# 12_fit_YX.net
KiCad netlist of a schematic drawn in Altium Designer
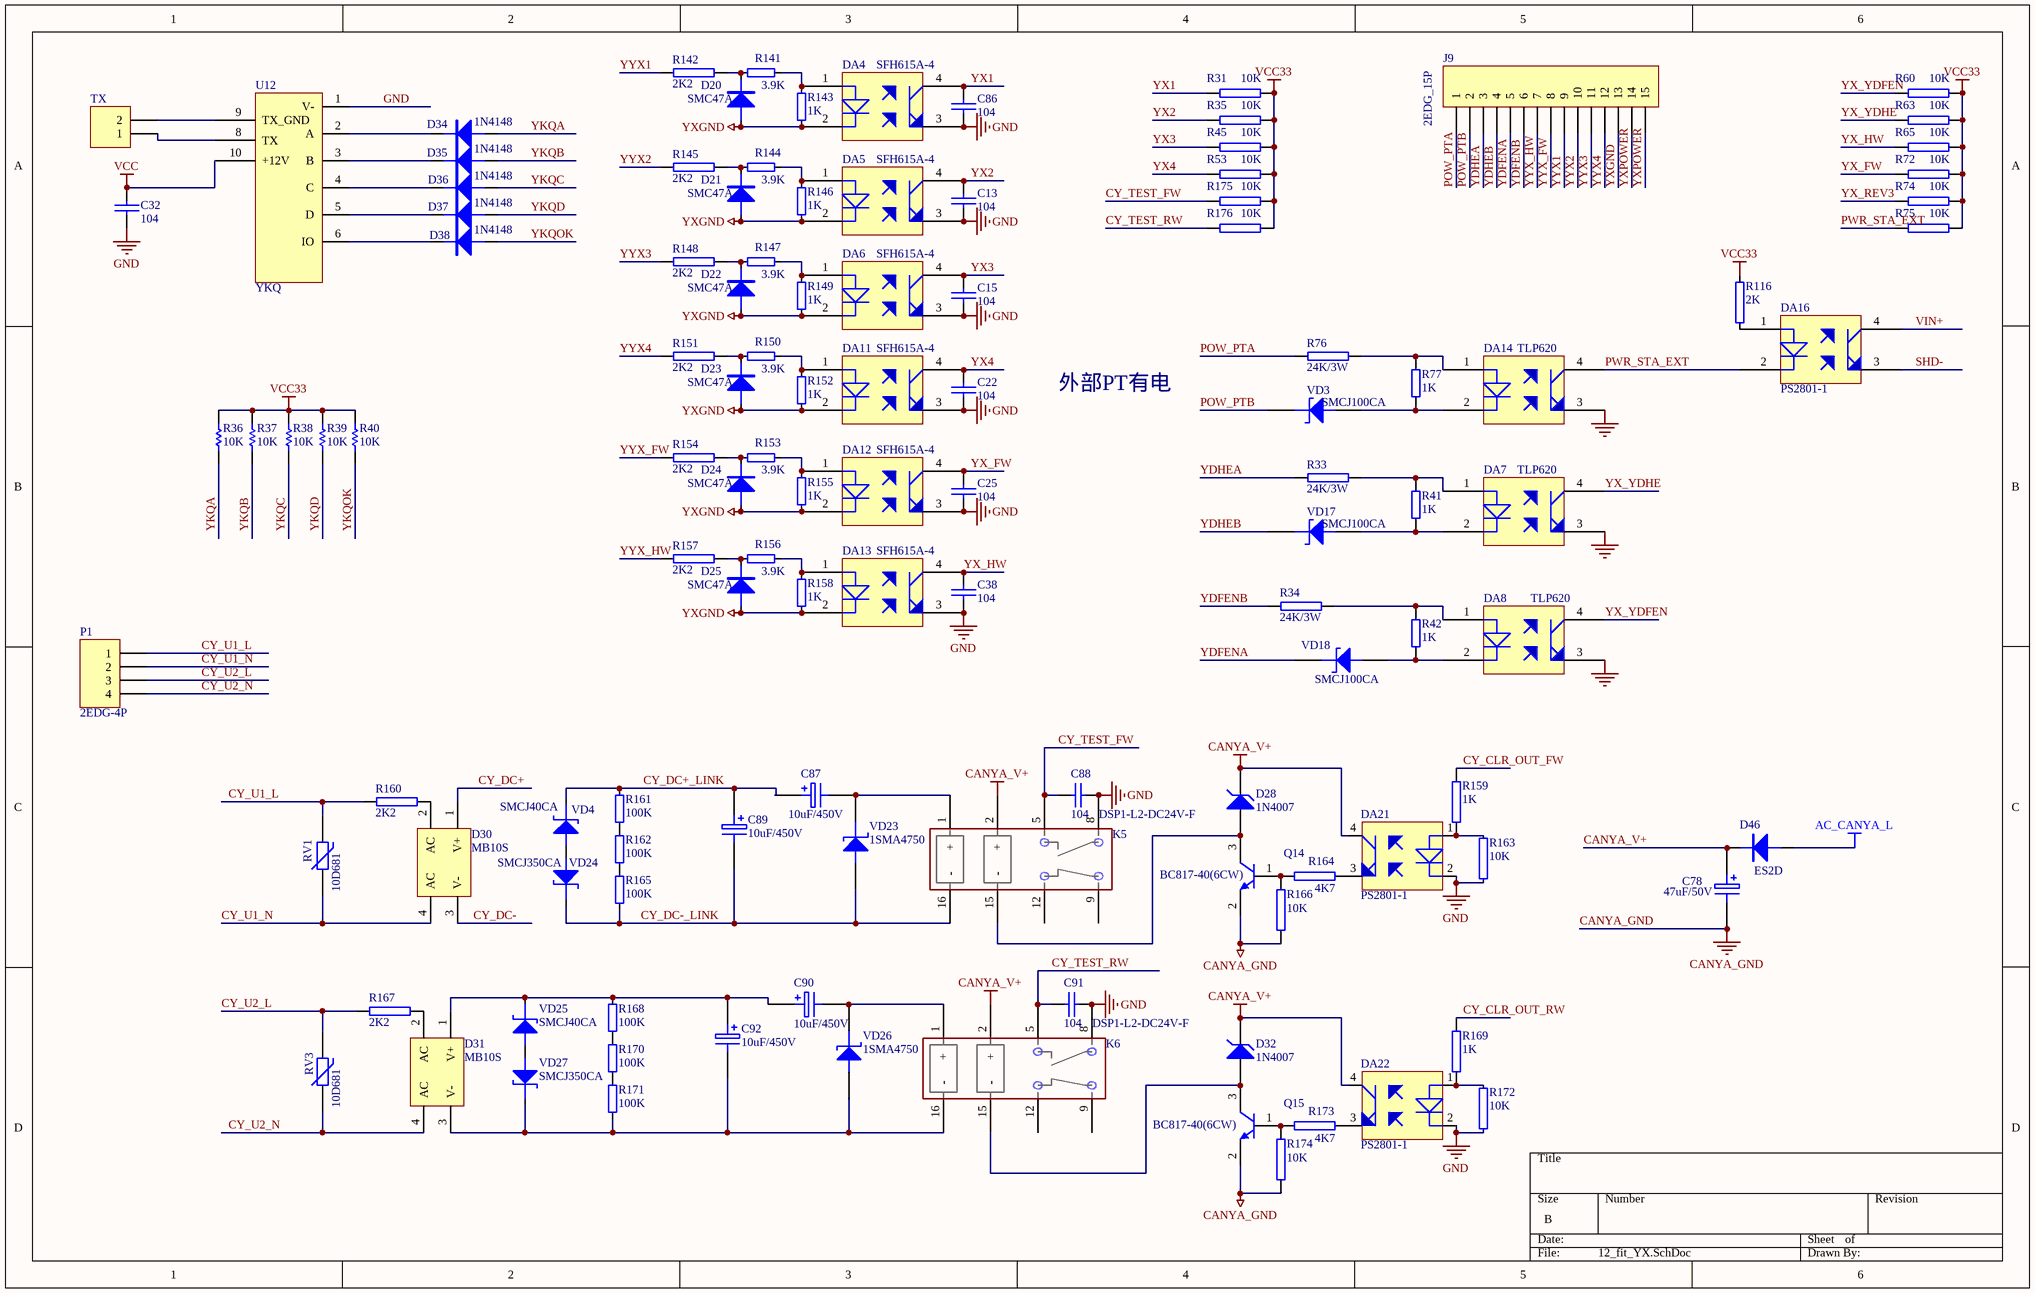
[diagram p0: 12_fit_YX.SchDoc]

(export (version "E")
  (design (tool "Eeschema 10.0.6"))
  (components
    (comp (ref "C13") (value "104") (footprint "smt:C1206") (libsource (lib "*") (part "CAP")))
    (comp (ref "C15") (value "104") (footprint "smt:C1206") (libsource (lib "*") (part "CAP")))
    (comp (ref "C22") (value "104") (footprint "smt:C1206") (libsource (lib "*") (part "CAP")))
    (comp (ref "C25") (value "104") (footprint "smt:C1206") (libsource (lib "*") (part "CAP")))
    (comp (ref "C32") (value "104") (footprint "smt:C1206") (libsource (lib "*") (part "CAP")))
    (comp (ref "C38") (value "104") (footprint "smt:C1206") (libsource (lib "*") (part "CAP")))
    (comp (ref "C78")
      (value "47uF/50V")
      (footprint "smt:47u/50V")
      (description "Electrolytic Capacitor")
      (libsource (lib "*") (part "ELECTRO1"))
    )
    (comp (ref "C86") (value "104") (footprint "smt:C1206") (libsource (lib "*") (part "CAP")))
    (comp (ref "C87")
      (value "10uF/450V")
      (footprint "smt:10u/450V")
      (description "Electrolytic Capacitor")
      (libsource (lib "*") (part "ELECTRO1"))
    )
    (comp (ref "C88") (value "104") (footprint "smt:C1206") (libsource (lib "*") (part "CAP")))
    (comp (ref "C89")
      (value "10uF/450V")
      (footprint "smt:10u/450V")
      (description "Electrolytic Capacitor")
      (libsource (lib "*") (part "ELECTRO1"))
    )
    (comp (ref "C90")
      (value "10uF/450V")
      (footprint "smt:10u/450V")
      (description "Electrolytic Capacitor")
      (libsource (lib "*") (part "ELECTRO1"))
    )
    (comp (ref "C91") (value "104") (footprint "smt:C1206") (libsource (lib "*") (part "CAP")))
    (comp (ref "C92")
      (value "10uF/450V")
      (footprint "smt:10u/450V")
      (description "Electrolytic Capacitor")
      (libsource (lib "*") (part "ELECTRO1"))
    )
    (comp (ref "D20")
      (value "SMC47A")
      (footprint "smt:DO-214AB")
      (description "Diode")
      (libsource (lib "*") (part "DIODE"))
    )
    (comp (ref "D21")
      (value "SMC47A")
      (footprint "smt:DO-214AB")
      (description "Diode")
      (libsource (lib "*") (part "DIODE"))
    )
    (comp (ref "D22")
      (value "SMC47A")
      (footprint "smt:DO-214AB")
      (description "Diode")
      (libsource (lib "*") (part "DIODE"))
    )
    (comp (ref "D23")
      (value "SMC47A")
      (footprint "smt:DO-214AB")
      (description "Diode")
      (libsource (lib "*") (part "DIODE"))
    )
    (comp (ref "D24")
      (value "SMC47A")
      (footprint "smt:DO-214AB")
      (description "Diode")
      (libsource (lib "*") (part "DIODE"))
    )
    (comp (ref "D25")
      (value "SMC47A")
      (footprint "smt:DO-214AB")
      (description "Diode")
      (libsource (lib "*") (part "DIODE"))
    )
    (comp (ref "D28")
      (value "1N4007")
      (footprint "smt:DO-214AC")
      (description "Zener Diode")
      (fields (field (name "PUBLISHER") "Altium Limited"))
      (libsource (lib "Miscellaneous Devices") (part "D Zener"))
    )
    (comp (ref "D30")
      (value "MB10S")
      (footprint "smt:TO-269AA")
      (description "Diode Bridge")
      (fields (field (name "PUBLISHER") "Altium Limited"))
      (libsource (lib "Miscellaneous Devices") (part "Bridge2"))
    )
    (comp (ref "D31")
      (value "MB10S")
      (footprint "smt:TO-269AA")
      (description "Diode Bridge")
      (fields (field (name "PUBLISHER") "Altium Limited"))
      (libsource (lib "Miscellaneous Devices") (part "Bridge2"))
    )
    (comp (ref "D32")
      (value "1N4007")
      (footprint "smt:DO-214AC")
      (description "Zener Diode")
      (fields (field (name "PUBLISHER") "Altium Limited"))
      (libsource (lib "Miscellaneous Devices") (part "D Zener"))
    )
    (comp (ref "D34")
      (value "1N4148")
      (footprint "smt:SMT_4148")
      (description "Diode")
      (libsource (lib "") (part "DIODE_1"))
    )
    (comp (ref "D35")
      (value "1N4148")
      (footprint "smt:SMT_4148")
      (description "Diode")
      (libsource (lib "") (part "DIODE_1"))
    )
    (comp (ref "D36")
      (value "1N4148")
      (footprint "smt:SMT_4148")
      (description "Diode")
      (libsource (lib "") (part "DIODE_1"))
    )
    (comp (ref "D37")
      (value "1N4148")
      (footprint "smt:SMT_4148")
      (description "Diode")
      (libsource (lib "") (part "DIODE_1"))
    )
    (comp (ref "D38")
      (value "1N4148")
      (footprint "smt:SMT_4148")
      (description "Diode")
      (libsource (lib "") (part "DIODE_1"))
    )
    (comp (ref "D46")
      (value "ES2D")
      (footprint "smt:DO-214AA")
      (description "Diode")
      (libsource (lib "") (part "DIODE_1"))
    )
    (comp (ref "DA4") (value "SFH615A-4") (footprint "smt:SFH615A-4") (libsource (lib "*") (part "TLP521-1")))
    (comp (ref "DA5") (value "SFH615A-4") (footprint "smt:SFH615A-4") (libsource (lib "*") (part "TLP521-1")))
    (comp (ref "DA6") (value "SFH615A-4") (footprint "smt:SFH615A-4") (libsource (lib "*") (part "TLP521-1")))
    (comp (ref "DA7") (value "TLP620") (footprint "smt:dip4") (libsource (lib "*") (part "TLP521-1")))
    (comp (ref "DA8") (value "TLP620") (footprint "smt:dip4") (libsource (lib "*") (part "TLP521-1")))
    (comp (ref "DA11")
      (value "SFH615A-4")
      (footprint "smt:SFH615A-4")
      (libsource (lib "*") (part "TLP521-1"))
    )
    (comp (ref "DA12")
      (value "SFH615A-4")
      (footprint "smt:SFH615A-4")
      (libsource (lib "*") (part "TLP521-1"))
    )
    (comp (ref "DA13")
      (value "SFH615A-4")
      (footprint "smt:SFH615A-4")
      (libsource (lib "*") (part "TLP521-1"))
    )
    (comp (ref "DA14") (value "TLP620") (footprint "smt:dip4") (libsource (lib "*") (part "TLP521-1")))
    (comp (ref "DA16") (value "PS2801-1") (footprint "SO-4") (libsource (lib "*") (part "TLP521-1")))
    (comp (ref "DA21") (value "PS2801-1") (footprint "SO-4") (libsource (lib "") (part "TLP521-1_1")))
    (comp (ref "DA22") (value "PS2801-1") (footprint "SO-4") (libsource (lib "") (part "TLP521-1_1")))
    (comp (ref "J9")
      (value "2EDG_15P")
      (footprint "MyCONNECTOR:XR_POWER5.08_15_弯")
      (description "Header, 15-Pin")
      (fields (field (name "PUBLISHER") "Altium Limited"))
      (libsource (lib "Miscellaneous Connectors") (part "Header 15"))
    )
    (comp (ref "K5")
      (value "DSP1-L2-DC24V-F")
      (footprint "DSP1-L2-DC24V-F")
      (libsource (lib "继电器") (part "DSP1-L2-DC24V-F"))
    )
    (comp (ref "K6")
      (value "DSP1-L2-DC24V-F")
      (footprint "DSP1-L2-DC24V-F")
      (libsource (lib "继电器") (part "DSP1-L2-DC24V-F"))
    )
    (comp (ref "P1")
      (value "2EDG-4P")
      (footprint "MyCONNECTOR:XR_POWER5.08_4_弯")
      (description "Header, 4-Pin")
      (fields (field (name "PUBLISHER") "Altium Limited"))
      (libsource (lib "Miscellaneous Connectors") (part "Header 4"))
    )
    (comp (ref "Q14")
      (value "BC817-40(6CW)")
      (footprint "smt:SOT-23")
      (description "NPN")
      (libsource (lib "Miscellaneous Devices LC") (part "SOT-23 2SC3356-T1B-A    S/YS档"))
    )
    (comp (ref "Q15")
      (value "BC817-40(6CW)")
      (footprint "smt:SOT-23")
      (description "NPN")
      (libsource (lib "Miscellaneous Devices LC") (part "SOT-23 2SC3356-T1B-A    S/YS档"))
    )
    (comp (ref "R31") (value "10K") (footprint "smt:R1206") (libsource (lib "*") (part "RES2")))
    (comp (ref "R33") (value "24K/3W") (footprint "smt:res-l5") (libsource (lib "*") (part "RES2")))
    (comp (ref "R34") (value "24K/3W") (footprint "smt:res-l5") (libsource (lib "*") (part "RES2")))
    (comp (ref "R35") (value "10K") (footprint "smt:R1206") (libsource (lib "*") (part "RES2")))
    (comp (ref "R36")
      (value "10K")
      (footprint "smt:R1206")
      (description "Resistor")
      (fields (field (name "PUBLISHER") "Altium Limited"))
      (libsource (lib "Miscellaneous Devices") (part "Res1"))
    )
    (comp (ref "R37")
      (value "10K")
      (footprint "smt:R1206")
      (description "Resistor")
      (fields (field (name "PUBLISHER") "Altium Limited"))
      (libsource (lib "Miscellaneous Devices") (part "Res1"))
    )
    (comp (ref "R38")
      (value "10K")
      (footprint "smt:R1206")
      (description "Resistor")
      (fields (field (name "PUBLISHER") "Altium Limited"))
      (libsource (lib "Miscellaneous Devices") (part "Res1"))
    )
    (comp (ref "R39")
      (value "10K")
      (footprint "smt:R1206")
      (description "Resistor")
      (fields (field (name "PUBLISHER") "Altium Limited"))
      (libsource (lib "Miscellaneous Devices") (part "Res1"))
    )
    (comp (ref "R40")
      (value "10K")
      (footprint "smt:R1206")
      (description "Resistor")
      (fields (field (name "PUBLISHER") "Altium Limited"))
      (libsource (lib "Miscellaneous Devices") (part "Res1"))
    )
    (comp (ref "R41") (value "1K") (footprint "smt:R1206") (libsource (lib "") (part "RES_1")))
    (comp (ref "R42") (value "1K") (footprint "smt:R1206") (libsource (lib "") (part "RES_1")))
    (comp (ref "R45") (value "10K") (footprint "smt:R1206") (libsource (lib "*") (part "RES2")))
    (comp (ref "R53") (value "10K") (footprint "smt:R1206") (libsource (lib "*") (part "RES2")))
    (comp (ref "R60") (value "10K") (footprint "smt:R1206") (libsource (lib "*") (part "RES2")))
    (comp (ref "R63") (value "10K") (footprint "smt:R1206") (libsource (lib "*") (part "RES2")))
    (comp (ref "R65") (value "10K") (footprint "smt:R1206") (libsource (lib "*") (part "RES2")))
    (comp (ref "R72") (value "10K") (footprint "smt:R1206") (libsource (lib "*") (part "RES2")))
    (comp (ref "R74") (value "10K") (footprint "smt:R1206") (libsource (lib "*") (part "RES2")))
    (comp (ref "R75") (value "10K") (footprint "smt:R1206") (libsource (lib "*") (part "RES2")))
    (comp (ref "R76") (value "24K/3W") (footprint "smt:res-l5") (libsource (lib "*") (part "RES2")))
    (comp (ref "R77") (value "1K") (footprint "smt:R1206") (libsource (lib "") (part "RES_1")))
    (comp (ref "R116") (value "2K") (footprint "smt:R1206") (libsource (lib "") (part "RES2_2")))
    (comp (ref "R141") (value "3.9K") (footprint "smt:R1206") (libsource (lib "*") (part "RES")))
    (comp (ref "R142") (value "2K2") (footprint "smt:res_0.5W-L-5.08") (libsource (lib "*") (part "RES2")))
    (comp (ref "R143") (value "1K") (footprint "smt:R1206") (libsource (lib "*") (part "RES")))
    (comp (ref "R144") (value "3.9K") (footprint "smt:R1206") (libsource (lib "*") (part "RES")))
    (comp (ref "R145") (value "2K2") (footprint "smt:res_0.5W-L-5.08") (libsource (lib "*") (part "RES2")))
    (comp (ref "R146") (value "1K") (footprint "smt:R1206") (libsource (lib "*") (part "RES")))
    (comp (ref "R147") (value "3.9K") (footprint "smt:R1206") (libsource (lib "*") (part "RES")))
    (comp (ref "R148") (value "2K2") (footprint "smt:res_0.5W-L-5.08") (libsource (lib "*") (part "RES2")))
    (comp (ref "R149") (value "1K") (footprint "smt:R1206") (libsource (lib "*") (part "RES")))
    (comp (ref "R150") (value "3.9K") (footprint "smt:R1206") (libsource (lib "*") (part "RES")))
    (comp (ref "R151") (value "2K2") (footprint "smt:res_0.5W-L-5.08") (libsource (lib "*") (part "RES2")))
    (comp (ref "R152") (value "1K") (footprint "smt:R1206") (libsource (lib "*") (part "RES")))
    (comp (ref "R153") (value "3.9K") (footprint "smt:R1206") (libsource (lib "*") (part "RES")))
    (comp (ref "R154") (value "2K2") (footprint "smt:res_0.5W-L-5.08") (libsource (lib "*") (part "RES2")))
    (comp (ref "R155") (value "1K") (footprint "smt:R1206") (libsource (lib "*") (part "RES")))
    (comp (ref "R156") (value "3.9K") (footprint "smt:R1206") (libsource (lib "*") (part "RES")))
    (comp (ref "R157") (value "2K2") (footprint "smt:res_0.5W-L-5.08") (libsource (lib "*") (part "RES2")))
    (comp (ref "R158") (value "1K") (footprint "smt:R1206") (libsource (lib "*") (part "RES")))
    (comp (ref "R159") (value "1K") (footprint "smt:R1206") (libsource (lib "*") (part "RES2")))
    (comp (ref "R160") (value "2K2") (footprint "smt:res_0.5W-L-5.08") (libsource (lib "*") (part "RES2")))
    (comp (ref "R161") (value "100K") (footprint "smt:R1206") (libsource (lib "*") (part "RES")))
    (comp (ref "R162") (value "100K") (footprint "smt:R1206") (libsource (lib "*") (part "RES")))
    (comp (ref "R163") (value "10K") (footprint "smt:R1206") (libsource (lib "") (part "RES2_1")))
    (comp (ref "R164") (value "4K7") (footprint "smt:R1206") (libsource (lib "*") (part "RES2")))
    (comp (ref "R165") (value "100K") (footprint "smt:R1206") (libsource (lib "*") (part "RES")))
    (comp (ref "R166") (value "10K") (footprint "smt:R1206") (libsource (lib "*") (part "RES2")))
    (comp (ref "R167") (value "2K2") (footprint "smt:res_0.5W-L-5.08") (libsource (lib "*") (part "RES2")))
    (comp (ref "R168") (value "100K") (footprint "smt:R1206") (libsource (lib "*") (part "RES")))
    (comp (ref "R169") (value "1K") (footprint "smt:R1206") (libsource (lib "*") (part "RES2")))
    (comp (ref "R170") (value "100K") (footprint "smt:R1206") (libsource (lib "*") (part "RES")))
    (comp (ref "R171") (value "100K") (footprint "smt:R1206") (libsource (lib "*") (part "RES")))
    (comp (ref "R172") (value "10K") (footprint "smt:R1206") (libsource (lib "") (part "RES2_1")))
    (comp (ref "R173") (value "4K7") (footprint "smt:R1206") (libsource (lib "*") (part "RES2")))
    (comp (ref "R174") (value "10K") (footprint "smt:R1206") (libsource (lib "*") (part "RES2")))
    (comp (ref "R175") (value "10K") (footprint "smt:R1206") (libsource (lib "*") (part "RES2")))
    (comp (ref "R176") (value "10K") (footprint "smt:R1206") (libsource (lib "*") (part "RES2")))
    (comp (ref "RV1") (value "10D681") (footprint "smt:NTC") (libsource (lib "*") (part "VARISTOR")))
    (comp (ref "RV3") (value "10D681") (footprint "smt:NTC") (libsource (lib "*") (part "VARISTOR")))
    (comp (ref "TX")
      (value "~")
      (footprint "MyCONNECTOR:XH_2.54*2")
      (description "Header, 2-Pin")
      (fields (field (name "PUBLISHER") "Altium Limited"))
      (libsource (lib "Miscellaneous Connectors") (part "Header 2"))
    )
    (comp (ref "U12")
      (value "YKQ")
      (footprint "希瑞模块线路板竖装:YKQ")
      (description "Zener Diode")
      (libsource (lib "*") (part "ZENER3_1"))
    )
    (comp (ref "VD3")
      (value "SMCJ100CA")
      (footprint "smt:DO-214AB")
      (description "双向TVS")
      (libsource (lib "*") (part "ZENER2"))
    )
    (comp (ref "VD4")
      (value "SMCJ40CA")
      (footprint "smt:DO-214AB")
      (description "Zener Diode")
      (libsource (lib "") (part "ZENER2_1"))
    )
    (comp (ref "VD17")
      (value "SMCJ100CA")
      (footprint "smt:DO-214AB")
      (description "双向TVS")
      (libsource (lib "*") (part "ZENER2"))
    )
    (comp (ref "VD18")
      (value "SMCJ100CA")
      (footprint "smt:DO-214AB")
      (description "Zener Diode")
      (libsource (lib "*") (part "ZENER2"))
    )
    (comp (ref "VD23")
      (value "1SMA4750")
      (footprint "smt:DO-214AC")
      (description "Zener Diode")
      (libsource (lib "*") (part "ZENER2"))
    )
    (comp (ref "VD24")
      (value "SMCJ350CA")
      (footprint "smt:DO-214AB")
      (description "Zener Diode")
      (libsource (lib "") (part "ZENER2_1"))
    )
    (comp (ref "VD25")
      (value "SMCJ40CA")
      (footprint "smt:DO-214AB")
      (description "Zener Diode")
      (libsource (lib "") (part "ZENER2_1"))
    )
    (comp (ref "VD26")
      (value "1SMA4750")
      (footprint "smt:DO-214AC")
      (description "Zener Diode")
      (libsource (lib "*") (part "ZENER2"))
    )
    (comp (ref "VD27")
      (value "SMCJ350CA")
      (footprint "smt:DO-214AB")
      (description "Zener Diode")
      (libsource (lib "") (part "ZENER2_1"))
    )
  )
  (nets
    (net (code "1") (name "/CY_CLR_OUT_FW") (class "Default")
      (node (ref "R159") (pin "2") (pintype "passive"))
    )
    (net (code "2") (name "/CY_CLR_OUT_RW") (class "Default")
      (node (ref "R169") (pin "2") (pintype "passive"))
    )
    (net (code "3") (name "/CY_DC+") (class "Default")
      (node (ref "D30") (pin "1") (pinfunction "V+_1") (pintype "passive"))
    )
    (net (code "4") (name "/CY_DC+_LINK") (class "Default")
      (node (ref "C87") (pin "1") (pinfunction "1_1") (pintype "passive"))
      (node (ref "C89") (pin "1") (pinfunction "1_1") (pintype "passive"))
      (node (ref "R161") (pin "2") (pinfunction "2_2") (pintype "passive"))
      (node (ref "VD4") (pin "2") (pinfunction "K_2") (pintype "passive"))
    )
    (net (code "5") (name "/CY_DC-") (class "Default")
      (node (ref "D30") (pin "3") (pinfunction "V-_3") (pintype "passive"))
    )
    (net (code "6") (name "/CY_DC-_LINK") (class "Default")
      (node (ref "C89") (pin "2") (pinfunction "2_2") (pintype "passive"))
      (node (ref "K5") (pin "16") (pinfunction "-_16") (pintype "passive"))
      (node (ref "R165") (pin "1") (pinfunction "1_1") (pintype "passive"))
      (node (ref "VD23") (pin "1") (pinfunction "A_1") (pintype "passive"))
      (node (ref "VD24") (pin "2") (pinfunction "K_2") (pintype "passive"))
    )
    (net (code "7") (name "/CY_TEST_FW") (class "Default")
      (node (ref "C88") (pin "2") (pintype "passive"))
      (node (ref "K5") (pin "5") (pinfunction "NO_5") (pintype "passive"))
      (node (ref "R175") (pin "1") (pintype "passive"))
    )
    (net (code "8") (name "/CY_TEST_RW") (class "Default")
      (node (ref "C91") (pin "2") (pintype "passive"))
      (node (ref "K6") (pin "5") (pinfunction "NO_5") (pintype "passive"))
      (node (ref "R176") (pin "1") (pintype "passive"))
    )
    (net (code "9") (name "/CY_U1_L") (class "Default")
      (node (ref "P1") (pin "1") (pinfunction "1_1") (pintype "passive"))
      (node (ref "R160") (pin "1") (pintype "passive"))
      (node (ref "RV1") (pin "2") (pinfunction "2_2") (pintype "passive"))
    )
    (net (code "10") (name "/CY_U1_N") (class "Default")
      (node (ref "D30") (pin "4") (pinfunction "AC_4") (pintype "passive"))
      (node (ref "P1") (pin "2") (pinfunction "2_2") (pintype "passive"))
      (node (ref "RV1") (pin "1") (pinfunction "1_1") (pintype "passive"))
    )
    (net (code "11") (name "/CY_U2_L") (class "Default")
      (node (ref "P1") (pin "3") (pinfunction "3_3") (pintype "passive"))
      (node (ref "R167") (pin "1") (pintype "passive"))
      (node (ref "RV3") (pin "2") (pinfunction "2_2") (pintype "passive"))
    )
    (net (code "12") (name "/CY_U2_N") (class "Default")
      (node (ref "D31") (pin "4") (pinfunction "AC_4") (pintype "passive"))
      (node (ref "P1") (pin "4") (pinfunction "4_4") (pintype "passive"))
      (node (ref "RV3") (pin "1") (pinfunction "1_1") (pintype "passive"))
    )
    (net (code "13") (name "/POW_PTA") (class "Default")
      (node (ref "J9") (pin "1") (pinfunction "1_1") (pintype "passive"))
      (node (ref "R76") (pin "1") (pintype "passive"))
    )
    (net (code "14") (name "/POW_PTB") (class "Default")
      (node (ref "J9") (pin "2") (pinfunction "2_2") (pintype "passive"))
      (node (ref "VD3") (pin "2") (pinfunction "K_2") (pintype "passive"))
    )
    (net (code "15") (name "/PWR_STA_EXT") (class "Default")
      (node (ref "DA14") (pin "4") (pintype "passive"))
      (node (ref "DA16") (pin "2") (pintype "passive"))
      (node (ref "R75") (pin "1") (pintype "passive"))
    )
    (net (code "16") (name "/SHD-") (class "Default") (node (ref "DA16") (pin "3") (pintype "passive")))
    (net (code "17") (name "/VIN+") (class "Default") (node (ref "DA16") (pin "4") (pintype "passive")))
    (net (code "18") (name "/YDFENA") (class "Default")
      (node (ref "J9") (pin "5") (pinfunction "5_5") (pintype "passive"))
      (node (ref "VD18") (pin "2") (pinfunction "K_2") (pintype "passive"))
    )
    (net (code "19") (name "/YDFENB") (class "Default")
      (node (ref "J9") (pin "6") (pinfunction "6_6") (pintype "passive"))
      (node (ref "R34") (pin "1") (pintype "passive"))
    )
    (net (code "20") (name "/YDHEA") (class "Default")
      (node (ref "J9") (pin "3") (pinfunction "3_3") (pintype "passive"))
      (node (ref "R33") (pin "1") (pintype "passive"))
    )
    (net (code "21") (name "/YDHEB") (class "Default")
      (node (ref "J9") (pin "4") (pinfunction "4_4") (pintype "passive"))
      (node (ref "VD17") (pin "2") (pinfunction "K_2") (pintype "passive"))
    )
    (net (code "22") (name "/YKQA") (class "Default")
      (node (ref "D34") (pin "1") (pinfunction "A_1") (pintype "passive"))
      (node (ref "R36") (pin "2") (pinfunction "2_2") (pintype "passive"))
    )
    (net (code "23") (name "/YKQB") (class "Default")
      (node (ref "D35") (pin "1") (pinfunction "A_1") (pintype "passive"))
      (node (ref "R37") (pin "1") (pinfunction "1_1") (pintype "passive"))
    )
    (net (code "24") (name "/YKQC") (class "Default")
      (node (ref "D36") (pin "1") (pinfunction "A_1") (pintype "passive"))
      (node (ref "R38") (pin "1") (pinfunction "1_1") (pintype "passive"))
    )
    (net (code "25") (name "/YKQD") (class "Default")
      (node (ref "D37") (pin "1") (pinfunction "A_1") (pintype "passive"))
      (node (ref "R39") (pin "1") (pinfunction "1_1") (pintype "passive"))
    )
    (net (code "26") (name "/YKQOK") (class "Default")
      (node (ref "D38") (pin "1") (pinfunction "A_1") (pintype "passive"))
      (node (ref "R40") (pin "1") (pinfunction "1_1") (pintype "passive"))
    )
    (net (code "27") (name "/YX1") (class "Default")
      (node (ref "C86") (pin "2") (pintype "passive"))
      (node (ref "DA4") (pin "4") (pintype "passive"))
      (node (ref "R31") (pin "1") (pintype "passive"))
    )
    (net (code "28") (name "/YX2") (class "Default")
      (node (ref "C13") (pin "2") (pintype "passive"))
      (node (ref "DA5") (pin "4") (pintype "passive"))
      (node (ref "R35") (pin "1") (pintype "passive"))
    )
    (net (code "29") (name "/YX3") (class "Default")
      (node (ref "C15") (pin "2") (pintype "passive"))
      (node (ref "DA6") (pin "4") (pintype "passive"))
      (node (ref "R45") (pin "1") (pintype "passive"))
    )
    (net (code "30") (name "/YX4") (class "Default")
      (node (ref "C22") (pin "2") (pintype "passive"))
      (node (ref "DA11") (pin "4") (pintype "passive"))
      (node (ref "R53") (pin "1") (pintype "passive"))
    )
    (net (code "31") (name "/YXPOWER") (class "Default")
      (node (ref "J9") (pin "14") (pinfunction "14_14") (pintype "passive"))
      (node (ref "J9") (pin "15") (pinfunction "15_15") (pintype "passive"))
    )
    (net (code "32") (name "/YX_FW") (class "Default")
      (node (ref "C25") (pin "2") (pintype "passive"))
      (node (ref "DA12") (pin "4") (pintype "passive"))
      (node (ref "R72") (pin "1") (pintype "passive"))
    )
    (net (code "33") (name "/YX_HW") (class "Default")
      (node (ref "C38") (pin "2") (pintype "passive"))
      (node (ref "DA13") (pin "4") (pintype "passive"))
      (node (ref "R65") (pin "1") (pintype "passive"))
    )
    (net (code "34") (name "/YX_REV3") (class "Default") (node (ref "R74") (pin "1") (pintype "passive")))
    (net (code "35") (name "/YX_YDFEN") (class "Default")
      (node (ref "DA8") (pin "4") (pintype "passive"))
      (node (ref "R60") (pin "1") (pintype "passive"))
    )
    (net (code "36") (name "/YX_YDHE") (class "Default")
      (node (ref "DA7") (pin "4") (pintype "passive"))
      (node (ref "R63") (pin "1") (pintype "passive"))
    )
    (net (code "37") (name "/YYX1") (class "Default")
      (node (ref "J9") (pin "9") (pinfunction "9_9") (pintype "passive"))
      (node (ref "R142") (pin "1") (pintype "passive"))
    )
    (net (code "38") (name "/YYX2") (class "Default")
      (node (ref "J9") (pin "10") (pinfunction "10_10") (pintype "passive"))
      (node (ref "R145") (pin "1") (pintype "passive"))
    )
    (net (code "39") (name "/YYX3") (class "Default")
      (node (ref "J9") (pin "11") (pinfunction "11_11") (pintype "passive"))
      (node (ref "R148") (pin "1") (pintype "passive"))
    )
    (net (code "40") (name "/YYX4") (class "Default")
      (node (ref "J9") (pin "12") (pinfunction "12_12") (pintype "passive"))
      (node (ref "R151") (pin "1") (pintype "passive"))
    )
    (net (code "41") (name "/YYX_FW") (class "Default")
      (node (ref "J9") (pin "8") (pinfunction "8_8") (pintype "passive"))
      (node (ref "R154") (pin "1") (pintype "passive"))
    )
    (net (code "42") (name "/YYX_HW") (class "Default")
      (node (ref "J9") (pin "7") (pinfunction "7_7") (pintype "passive"))
      (node (ref "R157") (pin "1") (pintype "passive"))
    )
    (net (code "43") (name "AC_CANYA_L") (class "Default")
      (node (ref "D46") (pin "1") (pinfunction "A_1") (pintype "passive"))
    )
    (net (code "44") (name "CANYA_GND") (class "Default")
      (node (ref "C78") (pin "2") (pinfunction "2_2") (pintype "passive"))
      (node (ref "Q14") (pin "2") (pinfunction "E_2") (pintype "passive"))
      (node (ref "Q15") (pin "2") (pinfunction "E_2") (pintype "passive"))
      (node (ref "R166") (pin "1") (pintype "passive"))
      (node (ref "R174") (pin "1") (pintype "passive"))
    )
    (net (code "45") (name "CANYA_V+") (class "Default")
      (node (ref "C78") (pin "1") (pinfunction "1_1") (pintype "passive"))
      (node (ref "D28") (pin "2") (pinfunction "K_2") (pintype "passive"))
      (node (ref "D32") (pin "2") (pinfunction "K_2") (pintype "passive"))
      (node (ref "D46") (pin "2") (pinfunction "K_2") (pintype "passive"))
      (node (ref "DA21") (pin "4") (pintype "passive"))
      (node (ref "DA22") (pin "4") (pintype "passive"))
      (node (ref "K5") (pin "2") (pinfunction "+_2") (pintype "passive"))
      (node (ref "K6") (pin "2") (pinfunction "+_2") (pintype "passive"))
    )
    (net (code "46") (name "GND") (class "Default")
      (node (ref "C13") (pin "1") (pintype "passive"))
      (node (ref "C15") (pin "1") (pintype "passive"))
      (node (ref "C22") (pin "1") (pintype "passive"))
      (node (ref "C25") (pin "1") (pintype "passive"))
      (node (ref "C32") (pin "1") (pintype "passive"))
      (node (ref "C38") (pin "1") (pintype "passive"))
      (node (ref "C86") (pin "1") (pintype "passive"))
      (node (ref "C88") (pin "1") (pintype "passive"))
      (node (ref "C91") (pin "1") (pintype "passive"))
      (node (ref "DA11") (pin "3") (pintype "passive"))
      (node (ref "DA12") (pin "3") (pintype "passive"))
      (node (ref "DA13") (pin "3") (pintype "passive"))
      (node (ref "DA14") (pin "3") (pintype "passive"))
      (node (ref "DA21") (pin "2") (pintype "passive"))
      (node (ref "DA22") (pin "2") (pintype "passive"))
      (node (ref "DA4") (pin "3") (pintype "passive"))
      (node (ref "DA5") (pin "3") (pintype "passive"))
      (node (ref "DA6") (pin "3") (pintype "passive"))
      (node (ref "DA7") (pin "3") (pintype "passive"))
      (node (ref "DA8") (pin "3") (pintype "passive"))
      (node (ref "K5") (pin "8") (pinfunction "NO_COM_8") (pintype "passive"))
      (node (ref "K6") (pin "8") (pinfunction "NO_COM_8") (pintype "passive"))
      (node (ref "R163") (pin "1") (pintype "passive"))
      (node (ref "R172") (pin "1") (pintype "passive"))
      (node (ref "U12") (pin "1") (pinfunction "V-_1") (pintype "passive"))
    )
    (net (code "47") (name "Net-(D20-K)") (class "Default")
      (node (ref "D20") (pin "2") (pinfunction "K_2") (pintype "passive"))
      (node (ref "R141") (pin "1") (pinfunction "1_1") (pintype "passive"))
      (node (ref "R142") (pin "2") (pintype "passive"))
    )
    (net (code "48") (name "Net-(D21-K)") (class "Default")
      (node (ref "D21") (pin "2") (pinfunction "K_2") (pintype "passive"))
      (node (ref "R144") (pin "1") (pinfunction "1_1") (pintype "passive"))
      (node (ref "R145") (pin "2") (pintype "passive"))
    )
    (net (code "49") (name "Net-(D22-K)") (class "Default")
      (node (ref "D22") (pin "2") (pinfunction "K_2") (pintype "passive"))
      (node (ref "R147") (pin "1") (pinfunction "1_1") (pintype "passive"))
      (node (ref "R148") (pin "2") (pintype "passive"))
    )
    (net (code "50") (name "Net-(D23-K)") (class "Default")
      (node (ref "D23") (pin "2") (pinfunction "K_2") (pintype "passive"))
      (node (ref "R150") (pin "1") (pinfunction "1_1") (pintype "passive"))
      (node (ref "R151") (pin "2") (pintype "passive"))
    )
    (net (code "51") (name "Net-(D24-K)") (class "Default")
      (node (ref "D24") (pin "2") (pinfunction "K_2") (pintype "passive"))
      (node (ref "R153") (pin "1") (pinfunction "1_1") (pintype "passive"))
      (node (ref "R154") (pin "2") (pintype "passive"))
    )
    (net (code "52") (name "Net-(D25-K)") (class "Default")
      (node (ref "D25") (pin "2") (pinfunction "K_2") (pintype "passive"))
      (node (ref "R156") (pin "1") (pinfunction "1_1") (pintype "passive"))
      (node (ref "R157") (pin "2") (pintype "passive"))
    )
    (net (code "53") (name "Net-(D28-A)") (class "Default")
      (node (ref "D28") (pin "1") (pinfunction "A_1") (pintype "passive"))
      (node (ref "K5") (pin "15") (pinfunction "-_15") (pintype "passive"))
      (node (ref "Q14") (pin "3") (pinfunction "C_3") (pintype "passive"))
    )
    (net (code "54") (name "Net-(D30-AC-Pad2)") (class "Default")
      (node (ref "D30") (pin "2") (pinfunction "AC_2") (pintype "passive"))
      (node (ref "R160") (pin "2") (pintype "passive"))
    )
    (net (code "55") (name "Net-(D31-AC-Pad2)") (class "Default")
      (node (ref "D31") (pin "2") (pinfunction "AC_2") (pintype "passive"))
      (node (ref "R167") (pin "2") (pintype "passive"))
    )
    (net (code "56") (name "Net-(D31-V+)") (class "Default")
      (node (ref "C90") (pin "1") (pinfunction "1_1") (pintype "passive"))
      (node (ref "C92") (pin "1") (pinfunction "1_1") (pintype "passive"))
      (node (ref "D31") (pin "1") (pinfunction "V+_1") (pintype "passive"))
      (node (ref "R168") (pin "2") (pinfunction "2_2") (pintype "passive"))
      (node (ref "VD25") (pin "2") (pinfunction "K_2") (pintype "passive"))
    )
    (net (code "57") (name "Net-(D31-V-)") (class "Default")
      (node (ref "C92") (pin "2") (pinfunction "2_2") (pintype "passive"))
      (node (ref "D31") (pin "3") (pinfunction "V-_3") (pintype "passive"))
      (node (ref "K6") (pin "16") (pinfunction "-_16") (pintype "passive"))
      (node (ref "R171") (pin "1") (pinfunction "1_1") (pintype "passive"))
      (node (ref "VD26") (pin "1") (pinfunction "A_1") (pintype "passive"))
      (node (ref "VD27") (pin "2") (pinfunction "K_2") (pintype "passive"))
    )
    (net (code "58") (name "Net-(D32-A)") (class "Default")
      (node (ref "D32") (pin "1") (pinfunction "A_1") (pintype "passive"))
      (node (ref "K6") (pin "15") (pinfunction "-_15") (pintype "passive"))
      (node (ref "Q15") (pin "3") (pinfunction "C_3") (pintype "passive"))
    )
    (net (code "59") (name "Net-(D34-K)") (class "Default")
      (node (ref "D34") (pin "2") (pinfunction "K_2") (pintype "passive"))
      (node (ref "U12") (pin "2") (pinfunction "A_2") (pintype "passive"))
    )
    (net (code "60") (name "Net-(D35-K)") (class "Default")
      (node (ref "D35") (pin "2") (pinfunction "K_2") (pintype "passive"))
      (node (ref "U12") (pin "3") (pinfunction "B_3") (pintype "passive"))
    )
    (net (code "61") (name "Net-(D36-K)") (class "Default")
      (node (ref "D36") (pin "2") (pinfunction "K_2") (pintype "passive"))
      (node (ref "U12") (pin "4") (pinfunction "C_4") (pintype "passive"))
    )
    (net (code "62") (name "Net-(D37-K)") (class "Default")
      (node (ref "D37") (pin "2") (pinfunction "K_2") (pintype "passive"))
      (node (ref "U12") (pin "5") (pinfunction "D_5") (pintype "passive"))
    )
    (net (code "63") (name "Net-(D38-K)") (class "Default")
      (node (ref "D38") (pin "2") (pinfunction "K_2") (pintype "passive"))
      (node (ref "U12") (pin "6") (pinfunction "IO_6") (pintype "passive"))
    )
    (net (code "64") (name "Net-(DA4-Pad1)") (class "Default")
      (node (ref "DA4") (pin "1") (pintype "passive"))
      (node (ref "R141") (pin "2") (pinfunction "2_2") (pintype "passive"))
      (node (ref "R143") (pin "1") (pinfunction "1_1") (pintype "passive"))
    )
    (net (code "65") (name "Net-(DA5-Pad1)") (class "Default")
      (node (ref "DA5") (pin "1") (pintype "passive"))
      (node (ref "R144") (pin "2") (pinfunction "2_2") (pintype "passive"))
      (node (ref "R146") (pin "1") (pinfunction "1_1") (pintype "passive"))
    )
    (net (code "66") (name "Net-(DA6-Pad1)") (class "Default")
      (node (ref "DA6") (pin "1") (pintype "passive"))
      (node (ref "R147") (pin "2") (pinfunction "2_2") (pintype "passive"))
      (node (ref "R149") (pin "1") (pinfunction "1_1") (pintype "passive"))
    )
    (net (code "67") (name "Net-(DA7-Pad1)") (class "Default")
      (node (ref "DA7") (pin "1") (pintype "passive"))
      (node (ref "R33") (pin "2") (pintype "passive"))
      (node (ref "R41") (pin "1") (pinfunction "1_1") (pintype "passive"))
    )
    (net (code "68") (name "Net-(DA8-Pad1)") (class "Default")
      (node (ref "DA8") (pin "1") (pintype "passive"))
      (node (ref "R34") (pin "2") (pintype "passive"))
      (node (ref "R42") (pin "2") (pinfunction "2_2") (pintype "passive"))
    )
    (net (code "69") (name "Net-(DA11-Pad1)") (class "Default")
      (node (ref "DA11") (pin "1") (pintype "passive"))
      (node (ref "R150") (pin "2") (pinfunction "2_2") (pintype "passive"))
      (node (ref "R152") (pin "1") (pinfunction "1_1") (pintype "passive"))
    )
    (net (code "70") (name "Net-(DA12-Pad1)") (class "Default")
      (node (ref "DA12") (pin "1") (pintype "passive"))
      (node (ref "R153") (pin "2") (pinfunction "2_2") (pintype "passive"))
      (node (ref "R155") (pin "1") (pinfunction "1_1") (pintype "passive"))
    )
    (net (code "71") (name "Net-(DA13-Pad1)") (class "Default")
      (node (ref "DA13") (pin "1") (pintype "passive"))
      (node (ref "R156") (pin "2") (pinfunction "2_2") (pintype "passive"))
      (node (ref "R158") (pin "1") (pinfunction "1_1") (pintype "passive"))
    )
    (net (code "72") (name "Net-(DA14-Pad1)") (class "Default")
      (node (ref "DA14") (pin "1") (pintype "passive"))
      (node (ref "R76") (pin "2") (pintype "passive"))
      (node (ref "R77") (pin "1") (pinfunction "1_1") (pintype "passive"))
    )
    (net (code "73") (name "Net-(DA16-Pad1)") (class "Default")
      (node (ref "DA16") (pin "1") (pintype "passive"))
      (node (ref "R116") (pin "2") (pinfunction "2_2") (pintype "passive"))
    )
    (net (code "74") (name "Net-(DA21-Pad1)") (class "Default")
      (node (ref "DA21") (pin "1") (pintype "passive"))
      (node (ref "R159") (pin "1") (pintype "passive"))
      (node (ref "R163") (pin "2") (pintype "passive"))
    )
    (net (code "75") (name "Net-(DA21-Pad3)") (class "Default")
      (node (ref "DA21") (pin "3") (pintype "passive"))
      (node (ref "R164") (pin "1") (pintype "passive"))
    )
    (net (code "76") (name "Net-(DA22-Pad1)") (class "Default")
      (node (ref "DA22") (pin "1") (pintype "passive"))
      (node (ref "R169") (pin "1") (pintype "passive"))
      (node (ref "R172") (pin "2") (pintype "passive"))
    )
    (net (code "77") (name "Net-(DA22-Pad3)") (class "Default")
      (node (ref "DA22") (pin "3") (pintype "passive"))
      (node (ref "R173") (pin "1") (pintype "passive"))
    )
    (net (code "78") (name "Net-(Q14-B)") (class "Default")
      (node (ref "Q14") (pin "1") (pinfunction "B_1") (pintype "passive"))
      (node (ref "R164") (pin "2") (pintype "passive"))
      (node (ref "R166") (pin "2") (pintype "passive"))
    )
    (net (code "79") (name "Net-(Q15-B)") (class "Default")
      (node (ref "Q15") (pin "1") (pinfunction "B_1") (pintype "passive"))
      (node (ref "R173") (pin "2") (pintype "passive"))
      (node (ref "R174") (pin "2") (pintype "passive"))
    )
    (net (code "80") (name "Net-(R161-Pad1)") (class "Default")
      (node (ref "R161") (pin "1") (pinfunction "1_1") (pintype "passive"))
      (node (ref "R162") (pin "2") (pinfunction "2_2") (pintype "passive"))
    )
    (net (code "81") (name "Net-(R162-Pad1)") (class "Default")
      (node (ref "R162") (pin "1") (pinfunction "1_1") (pintype "passive"))
      (node (ref "R165") (pin "2") (pinfunction "2_2") (pintype "passive"))
    )
    (net (code "82") (name "Net-(R168-Pad1)") (class "Default")
      (node (ref "R168") (pin "1") (pinfunction "1_1") (pintype "passive"))
      (node (ref "R170") (pin "2") (pinfunction "2_2") (pintype "passive"))
    )
    (net (code "83") (name "Net-(R170-Pad1)") (class "Default")
      (node (ref "R170") (pin "1") (pinfunction "1_1") (pintype "passive"))
      (node (ref "R171") (pin "2") (pinfunction "2_2") (pintype "passive"))
    )
    (net (code "84") (name "Net-(U12-TX)") (class "Default")
      (node (ref "TX") (pin "1") (pinfunction "1_1") (pintype "passive"))
      (node (ref "U12") (pin "8") (pinfunction "TX_8") (pintype "passive"))
    )
    (net (code "85") (name "Net-(U12-TX_GND)") (class "Default")
      (node (ref "TX") (pin "2") (pinfunction "2_2") (pintype "passive"))
      (node (ref "U12") (pin "9") (pinfunction "TX_GND_9") (pintype "passive"))
    )
    (net (code "86") (name "Net-(VD3-A)") (class "Default")
      (node (ref "DA14") (pin "2") (pintype "passive"))
      (node (ref "R77") (pin "2") (pinfunction "2_2") (pintype "passive"))
      (node (ref "VD3") (pin "1") (pinfunction "A_1") (pintype "passive"))
    )
    (net (code "87") (name "Net-(VD17-A)") (class "Default")
      (node (ref "DA7") (pin "2") (pintype "passive"))
      (node (ref "R41") (pin "2") (pinfunction "2_2") (pintype "passive"))
      (node (ref "VD17") (pin "1") (pinfunction "A_1") (pintype "passive"))
    )
    (net (code "88") (name "Net-(VD18-A)") (class "Default")
      (node (ref "DA8") (pin "2") (pintype "passive"))
      (node (ref "R42") (pin "1") (pinfunction "1_1") (pintype "passive"))
      (node (ref "VD18") (pin "1") (pinfunction "A_1") (pintype "passive"))
    )
    (net (code "89") (name "Net-(VD23-K)") (class "Default")
      (node (ref "C87") (pin "2") (pinfunction "2_2") (pintype "passive"))
      (node (ref "K5") (pin "1") (pinfunction "+_1") (pintype "passive"))
      (node (ref "VD23") (pin "2") (pinfunction "K_2") (pintype "passive"))
    )
    (net (code "90") (name "Net-(VD24-A)") (class "Default")
      (node (ref "VD24") (pin "1") (pinfunction "A_1") (pintype "passive"))
      (node (ref "VD4") (pin "1") (pinfunction "A_1") (pintype "passive"))
    )
    (net (code "91") (name "Net-(VD25-A)") (class "Default")
      (node (ref "VD25") (pin "1") (pinfunction "A_1") (pintype "passive"))
      (node (ref "VD27") (pin "1") (pinfunction "A_1") (pintype "passive"))
    )
    (net (code "92") (name "Net-(VD26-K)") (class "Default")
      (node (ref "C90") (pin "2") (pinfunction "2_2") (pintype "passive"))
      (node (ref "K6") (pin "1") (pinfunction "+_1") (pintype "passive"))
      (node (ref "VD26") (pin "2") (pinfunction "K_2") (pintype "passive"))
    )
    (net (code "93") (name "VCC") (class "Default")
      (node (ref "C32") (pin "2") (pintype "passive"))
      (node (ref "U12") (pin "10") (pinfunction "+12V_10") (pintype "passive"))
    )
    (net (code "94") (name "VCC33") (class "Default")
      (node (ref "R116") (pin "1") (pinfunction "1_1") (pintype "passive"))
      (node (ref "R175") (pin "2") (pintype "passive"))
      (node (ref "R176") (pin "2") (pintype "passive"))
      (node (ref "R31") (pin "2") (pintype "passive"))
      (node (ref "R35") (pin "2") (pintype "passive"))
      (node (ref "R36") (pin "1") (pinfunction "1_1") (pintype "passive"))
      (node (ref "R37") (pin "2") (pinfunction "2_2") (pintype "passive"))
      (node (ref "R38") (pin "2") (pinfunction "2_2") (pintype "passive"))
      (node (ref "R39") (pin "2") (pinfunction "2_2") (pintype "passive"))
      (node (ref "R40") (pin "2") (pinfunction "2_2") (pintype "passive"))
      (node (ref "R45") (pin "2") (pintype "passive"))
      (node (ref "R53") (pin "2") (pintype "passive"))
      (node (ref "R60") (pin "2") (pintype "passive"))
      (node (ref "R63") (pin "2") (pintype "passive"))
      (node (ref "R65") (pin "2") (pintype "passive"))
      (node (ref "R72") (pin "2") (pintype "passive"))
      (node (ref "R74") (pin "2") (pintype "passive"))
      (node (ref "R75") (pin "2") (pintype "passive"))
    )
    (net (code "95") (name "YXGND") (class "Default")
      (node (ref "D20") (pin "1") (pinfunction "A_1") (pintype "passive"))
      (node (ref "D21") (pin "1") (pinfunction "A_1") (pintype "passive"))
      (node (ref "D22") (pin "1") (pinfunction "A_1") (pintype "passive"))
      (node (ref "D23") (pin "1") (pinfunction "A_1") (pintype "passive"))
      (node (ref "D24") (pin "1") (pinfunction "A_1") (pintype "passive"))
      (node (ref "D25") (pin "1") (pinfunction "A_1") (pintype "passive"))
      (node (ref "DA11") (pin "2") (pintype "passive"))
      (node (ref "DA12") (pin "2") (pintype "passive"))
      (node (ref "DA13") (pin "2") (pintype "passive"))
      (node (ref "DA4") (pin "2") (pintype "passive"))
      (node (ref "DA5") (pin "2") (pintype "passive"))
      (node (ref "DA6") (pin "2") (pintype "passive"))
      (node (ref "J9") (pin "13") (pinfunction "13_13") (pintype "passive"))
      (node (ref "R143") (pin "2") (pinfunction "2_2") (pintype "passive"))
      (node (ref "R146") (pin "2") (pinfunction "2_2") (pintype "passive"))
      (node (ref "R149") (pin "2") (pinfunction "2_2") (pintype "passive"))
      (node (ref "R152") (pin "2") (pinfunction "2_2") (pintype "passive"))
      (node (ref "R155") (pin "2") (pinfunction "2_2") (pintype "passive"))
      (node (ref "R158") (pin "2") (pinfunction "2_2") (pintype "passive"))
    )
    (net (code "96") (name "unconnected-(K5-NC-Pad12)") (class "Default")
      (node (ref "K5") (pin "12") (pinfunction "NC_12") (pintype "passive"))
    )
    (net (code "97") (name "unconnected-(K5-NC_COM-Pad9)") (class "Default")
      (node (ref "K5") (pin "9") (pinfunction "NC_COM_9") (pintype "passive"))
    )
    (net (code "98") (name "unconnected-(K6-NC-Pad12)") (class "Default")
      (node (ref "K6") (pin "12") (pinfunction "NC_12") (pintype "passive"))
    )
    (net (code "99") (name "unconnected-(K6-NC_COM-Pad9)") (class "Default")
      (node (ref "K6") (pin "9") (pinfunction "NC_COM_9") (pintype "passive"))
    )
  )
)
